# Motors.net
KiCad netlist of a schematic drawn in Altium Designer
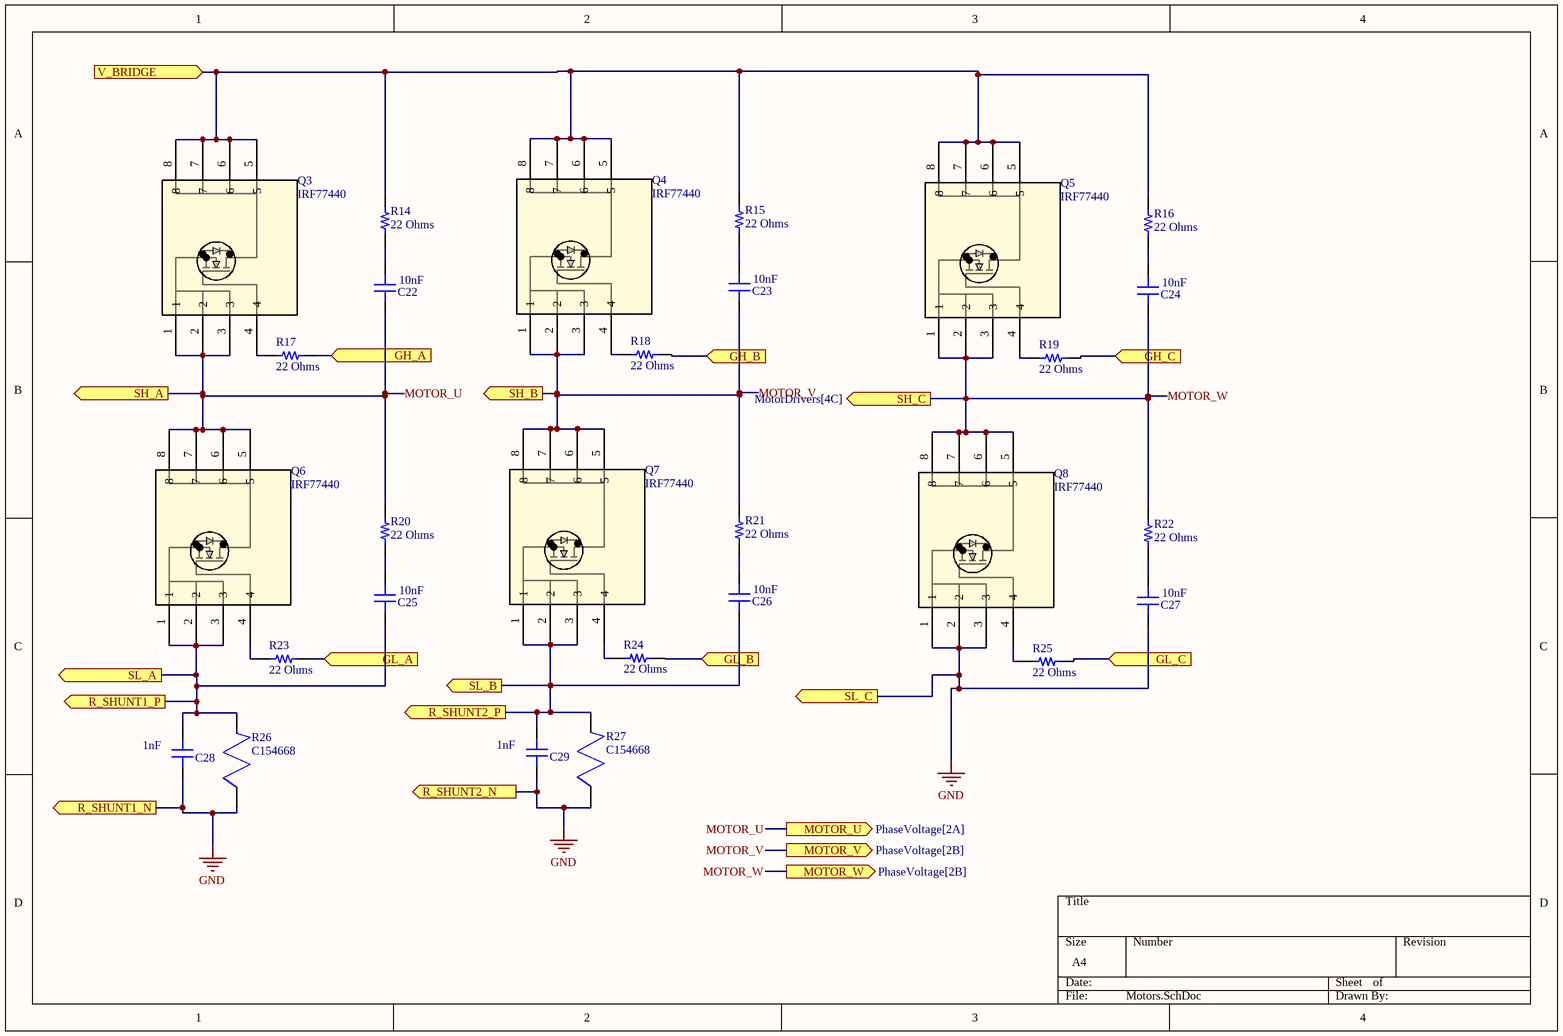
[diagram p0: Motors.SchDoc]

(export (version "E")
  (design (tool "Eeschema 10.0.6"))
  (components
    (comp (ref "C22")
      (value "10nF")
      (footprint "CAP 0603_1608")
      (description "CAP CER 1000PF 10V X7R 0603")
      (fields (field (name "PART NUMBER") "0603ZC102KAT2A") (field (name "MANUFACTURER") "AVX Corporation"))
      (libsource (lib "Celestial Altium Library - altium_library (4)") (part "Capacitor"))
    )
    (comp (ref "C23")
      (value "10nF")
      (footprint "CAP 0603_1608")
      (description "CAP CER 1000PF 10V X7R 0603")
      (fields (field (name "PART NUMBER") "0603ZC102KAT2A") (field (name "MANUFACTURER") "AVX Corporation"))
      (libsource (lib "Celestial Altium Library - altium_library (4)") (part "Capacitor"))
    )
    (comp (ref "C24")
      (value "10nF")
      (footprint "CAP 0603_1608")
      (description "CAP CER 1000PF 10V X7R 0603")
      (fields (field (name "PART NUMBER") "0603ZC102KAT2A") (field (name "MANUFACTURER") "AVX Corporation"))
      (libsource (lib "Celestial Altium Library - altium_library (4)") (part "Capacitor"))
    )
    (comp (ref "C25")
      (value "10nF")
      (footprint "CAP 0603_1608")
      (description "CAP CER 1000PF 10V X7R 0603")
      (fields (field (name "PART NUMBER") "0603ZC102KAT2A") (field (name "MANUFACTURER") "AVX Corporation"))
      (libsource (lib "Celestial Altium Library - altium_library (4)") (part "Capacitor"))
    )
    (comp (ref "C26")
      (value "10nF")
      (footprint "CAP 0603_1608")
      (description "CAP CER 1000PF 10V X7R 0603")
      (fields (field (name "PART NUMBER") "0603ZC102KAT2A") (field (name "MANUFACTURER") "AVX Corporation"))
      (libsource (lib "Celestial Altium Library - altium_library (4)") (part "Capacitor"))
    )
    (comp (ref "C27")
      (value "10nF")
      (footprint "CAP 0603_1608")
      (description "CAP CER 1000PF 10V X7R 0603")
      (fields (field (name "PART NUMBER") "0603ZC102KAT2A") (field (name "MANUFACTURER") "AVX Corporation"))
      (libsource (lib "Celestial Altium Library - altium_library (4)") (part "Capacitor"))
    )
    (comp (ref "C28")
      (value "1nF")
      (footprint "CAP 0603_1608")
      (description "CAP CER 1000PF 10V X7R 0603")
      (fields (field (name "PART NUMBER") "0603ZC102KAT2A") (field (name "MANUFACTURER") "AVX Corporation"))
      (libsource (lib "Celestial Altium Library - altium_library (4)") (part "Capacitor"))
    )
    (comp (ref "C29")
      (value "1nF")
      (footprint "CAP 0603_1608")
      (description "CAP CER 1000PF 10V X7R 0603")
      (fields (field (name "PART NUMBER") "0603ZC102KAT2A") (field (name "MANUFACTURER") "AVX Corporation"))
      (libsource (lib "Celestial Altium Library - altium_library (4)") (part "Capacitor"))
    )
    (comp (ref "Q3") (value "IRF77440") (footprint "IRF77440") (libsource (lib "Schlib1") (part "IRF77440")))
    (comp (ref "Q4") (value "IRF77440") (footprint "IRF77440") (libsource (lib "Schlib1") (part "IRF77440")))
    (comp (ref "Q5") (value "IRF77440") (footprint "IRF77440") (libsource (lib "Schlib1") (part "IRF77440")))
    (comp (ref "Q6") (value "IRF77440") (footprint "IRF77440") (libsource (lib "Schlib1") (part "IRF77440")))
    (comp (ref "Q7") (value "IRF77440") (footprint "IRF77440") (libsource (lib "Schlib1") (part "IRF77440")))
    (comp (ref "Q8") (value "IRF77440") (footprint "IRF77440") (libsource (lib "Schlib1") (part "IRF77440")))
    (comp (ref "R14")
      (value "22 Ohms")
      (footprint "RES 0402_1005")
      (description "ANTI-SURGE CHIP RESISTORS")
      (fields (field (name "PART NUMBER") "ESR01MZPF47R0") (field (name "MANUFACTURER") "Rohm Semiconductor"))
      (libsource (lib "Celestial Altium Library - altium_library (4)") (part "Resistor"))
    )
    (comp (ref "R15")
      (value "22 Ohms")
      (footprint "RES 0402_1005")
      (description "ANTI-SURGE CHIP RESISTORS")
      (fields (field (name "PART NUMBER") "ESR01MZPF47R0") (field (name "MANUFACTURER") "Rohm Semiconductor"))
      (libsource (lib "Celestial Altium Library - altium_library (4)") (part "Resistor"))
    )
    (comp (ref "R16")
      (value "22 Ohms")
      (footprint "RES 0402_1005")
      (description "ANTI-SURGE CHIP RESISTORS")
      (fields (field (name "PART NUMBER") "ESR01MZPF47R0") (field (name "MANUFACTURER") "Rohm Semiconductor"))
      (libsource (lib "Celestial Altium Library - altium_library (4)") (part "Resistor"))
    )
    (comp (ref "R17")
      (value "22 Ohms")
      (footprint "RES 0402_1005")
      (description "ANTI-SURGE CHIP RESISTORS")
      (fields (field (name "PART NUMBER") "ESR01MZPF47R0") (field (name "MANUFACTURER") "Rohm Semiconductor"))
      (libsource (lib "Celestial Altium Library - altium_library (4)") (part "Resistor"))
    )
    (comp (ref "R18")
      (value "22 Ohms")
      (footprint "RES 0402_1005")
      (description "ANTI-SURGE CHIP RESISTORS")
      (fields (field (name "PART NUMBER") "ESR01MZPF47R0") (field (name "MANUFACTURER") "Rohm Semiconductor"))
      (libsource (lib "Celestial Altium Library - altium_library (4)") (part "Resistor"))
    )
    (comp (ref "R19")
      (value "22 Ohms")
      (footprint "RES 0402_1005")
      (description "ANTI-SURGE CHIP RESISTORS")
      (fields (field (name "PART NUMBER") "ESR01MZPF47R0") (field (name "MANUFACTURER") "Rohm Semiconductor"))
      (libsource (lib "Celestial Altium Library - altium_library (4)") (part "Resistor"))
    )
    (comp (ref "R20")
      (value "22 Ohms")
      (footprint "RES 0402_1005")
      (description "ANTI-SURGE CHIP RESISTORS")
      (fields (field (name "PART NUMBER") "ESR01MZPF47R0") (field (name "MANUFACTURER") "Rohm Semiconductor"))
      (libsource (lib "Celestial Altium Library - altium_library (4)") (part "Resistor"))
    )
    (comp (ref "R21")
      (value "22 Ohms")
      (footprint "RES 0402_1005")
      (description "ANTI-SURGE CHIP RESISTORS")
      (fields (field (name "PART NUMBER") "ESR01MZPF47R0") (field (name "MANUFACTURER") "Rohm Semiconductor"))
      (libsource (lib "Celestial Altium Library - altium_library (4)") (part "Resistor"))
    )
    (comp (ref "R22")
      (value "22 Ohms")
      (footprint "RES 0402_1005")
      (description "ANTI-SURGE CHIP RESISTORS")
      (fields (field (name "PART NUMBER") "ESR01MZPF47R0") (field (name "MANUFACTURER") "Rohm Semiconductor"))
      (libsource (lib "Celestial Altium Library - altium_library (4)") (part "Resistor"))
    )
    (comp (ref "R23")
      (value "22 Ohms")
      (footprint "RES 0402_1005")
      (description "ANTI-SURGE CHIP RESISTORS")
      (fields (field (name "PART NUMBER") "ESR01MZPF47R0") (field (name "MANUFACTURER") "Rohm Semiconductor"))
      (libsource (lib "Celestial Altium Library - altium_library (4)") (part "Resistor"))
    )
    (comp (ref "R24")
      (value "22 Ohms")
      (footprint "RES 0402_1005")
      (description "ANTI-SURGE CHIP RESISTORS")
      (fields (field (name "PART NUMBER") "ESR01MZPF47R0") (field (name "MANUFACTURER") "Rohm Semiconductor"))
      (libsource (lib "Celestial Altium Library - altium_library (4)") (part "Resistor"))
    )
    (comp (ref "R25")
      (value "22 Ohms")
      (footprint "RES 0402_1005")
      (description "ANTI-SURGE CHIP RESISTORS")
      (fields (field (name "PART NUMBER") "ESR01MZPF47R0") (field (name "MANUFACTURER") "Rohm Semiconductor"))
      (libsource (lib "Celestial Altium Library - altium_library (4)") (part "Resistor"))
    )
    (comp (ref "R26") (value "C154668") (footprint "C154668") (libsource (lib "Schlib1") (part "C154668")))
    (comp (ref "R27") (value "C154668") (footprint "C154668") (libsource (lib "Schlib1") (part "C154668")))
  )
  (nets
    (net (code "1") (name "/GH_A") (class "Default")
      (node (ref "R17") (pin "2") (pinfunction "2_2") (pintype "passive"))
    )
    (net (code "2") (name "/GH_B") (class "Default")
      (node (ref "R18") (pin "2") (pinfunction "2_2") (pintype "passive"))
    )
    (net (code "3") (name "/GH_C") (class "Default")
      (node (ref "R19") (pin "2") (pinfunction "2_2") (pintype "passive"))
    )
    (net (code "4") (name "/GL_A") (class "Default")
      (node (ref "R23") (pin "2") (pinfunction "2_2") (pintype "passive"))
    )
    (net (code "5") (name "/GL_B") (class "Default")
      (node (ref "R24") (pin "2") (pinfunction "2_2") (pintype "passive"))
    )
    (net (code "6") (name "/GL_C") (class "Default")
      (node (ref "R25") (pin "2") (pinfunction "2_2") (pintype "passive"))
    )
    (net (code "7") (name "/MOTOR_U") (class "Default")
      (node (ref "C22") (pin "1") (pinfunction "1_1") (pintype "passive"))
      (node (ref "Q3") (pin "1") (pinfunction "1_1") (pintype "passive"))
      (node (ref "Q3") (pin "2") (pinfunction "2_2") (pintype "passive"))
      (node (ref "Q3") (pin "3") (pinfunction "3_3") (pintype "passive"))
      (node (ref "Q6") (pin "5") (pinfunction "5_5") (pintype "passive"))
      (node (ref "Q6") (pin "6") (pinfunction "6_6") (pintype "passive"))
      (node (ref "Q6") (pin "7") (pinfunction "7_7") (pintype "passive"))
      (node (ref "Q6") (pin "8") (pinfunction "8_8") (pintype "passive"))
      (node (ref "R20") (pin "2") (pinfunction "2_2") (pintype "passive"))
    )
    (net (code "8") (name "/MOTOR_V") (class "Default")
      (node (ref "C23") (pin "1") (pinfunction "1_1") (pintype "passive"))
      (node (ref "Q4") (pin "1") (pinfunction "1_1") (pintype "passive"))
      (node (ref "Q4") (pin "2") (pinfunction "2_2") (pintype "passive"))
      (node (ref "Q4") (pin "3") (pinfunction "3_3") (pintype "passive"))
      (node (ref "Q7") (pin "5") (pinfunction "5_5") (pintype "passive"))
      (node (ref "Q7") (pin "6") (pinfunction "6_6") (pintype "passive"))
      (node (ref "Q7") (pin "7") (pinfunction "7_7") (pintype "passive"))
      (node (ref "Q7") (pin "8") (pinfunction "8_8") (pintype "passive"))
      (node (ref "R21") (pin "2") (pinfunction "2_2") (pintype "passive"))
    )
    (net (code "9") (name "/MOTOR_W") (class "Default")
      (node (ref "C24") (pin "1") (pinfunction "1_1") (pintype "passive"))
      (node (ref "Q5") (pin "1") (pinfunction "1_1") (pintype "passive"))
      (node (ref "Q5") (pin "2") (pinfunction "2_2") (pintype "passive"))
      (node (ref "Q5") (pin "3") (pinfunction "3_3") (pintype "passive"))
      (node (ref "Q8") (pin "5") (pinfunction "5_5") (pintype "passive"))
      (node (ref "Q8") (pin "6") (pinfunction "6_6") (pintype "passive"))
      (node (ref "Q8") (pin "7") (pinfunction "7_7") (pintype "passive"))
      (node (ref "Q8") (pin "8") (pinfunction "8_8") (pintype "passive"))
      (node (ref "R22") (pin "2") (pinfunction "2_2") (pintype "passive"))
    )
    (net (code "10") (name "/R_SHUNT1_P") (class "Default")
      (node (ref "C25") (pin "1") (pinfunction "1_1") (pintype "passive"))
      (node (ref "C28") (pin "2") (pinfunction "2_2") (pintype "passive"))
      (node (ref "Q6") (pin "1") (pinfunction "1_1") (pintype "passive"))
      (node (ref "Q6") (pin "2") (pinfunction "2_2") (pintype "passive"))
      (node (ref "Q6") (pin "3") (pinfunction "3_3") (pintype "passive"))
      (node (ref "R26") (pin "2") (pinfunction "0_2") (pintype "passive"))
    )
    (net (code "11") (name "/R_SHUNT2_P") (class "Default")
      (node (ref "C26") (pin "1") (pinfunction "1_1") (pintype "passive"))
      (node (ref "C29") (pin "2") (pinfunction "2_2") (pintype "passive"))
      (node (ref "Q7") (pin "1") (pinfunction "1_1") (pintype "passive"))
      (node (ref "Q7") (pin "2") (pinfunction "2_2") (pintype "passive"))
      (node (ref "Q7") (pin "3") (pinfunction "3_3") (pintype "passive"))
      (node (ref "R27") (pin "2") (pinfunction "0_2") (pintype "passive"))
    )
    (net (code "13") (name "/V_BRIDGE") (class "Default")
      (node (ref "Q3") (pin "5") (pinfunction "5_5") (pintype "passive"))
      (node (ref "Q3") (pin "6") (pinfunction "6_6") (pintype "passive"))
      (node (ref "Q3") (pin "7") (pinfunction "7_7") (pintype "passive"))
      (node (ref "Q3") (pin "8") (pinfunction "8_8") (pintype "passive"))
      (node (ref "Q4") (pin "5") (pinfunction "5_5") (pintype "passive"))
      (node (ref "Q4") (pin "6") (pinfunction "6_6") (pintype "passive"))
      (node (ref "Q4") (pin "7") (pinfunction "7_7") (pintype "passive"))
      (node (ref "Q4") (pin "8") (pinfunction "8_8") (pintype "passive"))
      (node (ref "Q5") (pin "5") (pinfunction "5_5") (pintype "passive"))
      (node (ref "Q5") (pin "6") (pinfunction "6_6") (pintype "passive"))
      (node (ref "Q5") (pin "7") (pinfunction "7_7") (pintype "passive"))
      (node (ref "Q5") (pin "8") (pinfunction "8_8") (pintype "passive"))
      (node (ref "R14") (pin "2") (pinfunction "2_2") (pintype "passive"))
      (node (ref "R15") (pin "2") (pinfunction "2_2") (pintype "passive"))
      (node (ref "R16") (pin "2") (pinfunction "2_2") (pintype "passive"))
    )
    (net (code "14") (name "GND") (class "Default")
      (node (ref "C27") (pin "1") (pinfunction "1_1") (pintype "passive"))
      (node (ref "C28") (pin "1") (pinfunction "1_1") (pintype "passive"))
      (node (ref "C29") (pin "1") (pinfunction "1_1") (pintype "passive"))
      (node (ref "Q8") (pin "1") (pinfunction "1_1") (pintype "passive"))
      (node (ref "Q8") (pin "2") (pinfunction "2_2") (pintype "passive"))
      (node (ref "Q8") (pin "3") (pinfunction "3_3") (pintype "passive"))
      (node (ref "R26") (pin "1") (pinfunction "1_1") (pintype "passive"))
      (node (ref "R27") (pin "1") (pinfunction "1_1") (pintype "passive"))
    )
    (net (code "15") (name "Net-(C22-Pad2)") (class "Default")
      (node (ref "C22") (pin "2") (pinfunction "2_2") (pintype "passive"))
      (node (ref "R14") (pin "1") (pinfunction "1_1") (pintype "passive"))
    )
    (net (code "16") (name "Net-(C23-Pad2)") (class "Default")
      (node (ref "C23") (pin "2") (pinfunction "2_2") (pintype "passive"))
      (node (ref "R15") (pin "1") (pinfunction "1_1") (pintype "passive"))
    )
    (net (code "17") (name "Net-(C24-Pad2)") (class "Default")
      (node (ref "C24") (pin "2") (pinfunction "2_2") (pintype "passive"))
      (node (ref "R16") (pin "1") (pinfunction "1_1") (pintype "passive"))
    )
    (net (code "18") (name "Net-(C25-Pad2)") (class "Default")
      (node (ref "C25") (pin "2") (pinfunction "2_2") (pintype "passive"))
      (node (ref "R20") (pin "1") (pinfunction "1_1") (pintype "passive"))
    )
    (net (code "19") (name "Net-(C26-Pad2)") (class "Default")
      (node (ref "C26") (pin "2") (pinfunction "2_2") (pintype "passive"))
      (node (ref "R21") (pin "1") (pinfunction "1_1") (pintype "passive"))
    )
    (net (code "20") (name "Net-(C27-Pad2)") (class "Default")
      (node (ref "C27") (pin "2") (pinfunction "2_2") (pintype "passive"))
      (node (ref "R22") (pin "1") (pinfunction "1_1") (pintype "passive"))
    )
    (net (code "21") (name "Net-(Q3-Pad4)") (class "Default")
      (node (ref "Q3") (pin "4") (pinfunction "4_4") (pintype "passive"))
      (node (ref "R17") (pin "1") (pinfunction "1_1") (pintype "passive"))
    )
    (net (code "22") (name "Net-(Q4-Pad4)") (class "Default")
      (node (ref "Q4") (pin "4") (pinfunction "4_4") (pintype "passive"))
      (node (ref "R18") (pin "1") (pinfunction "1_1") (pintype "passive"))
    )
    (net (code "23") (name "Net-(Q5-Pad4)") (class "Default")
      (node (ref "Q5") (pin "4") (pinfunction "4_4") (pintype "passive"))
      (node (ref "R19") (pin "1") (pinfunction "1_1") (pintype "passive"))
    )
    (net (code "24") (name "Net-(Q6-Pad4)") (class "Default")
      (node (ref "Q6") (pin "4") (pinfunction "4_4") (pintype "passive"))
      (node (ref "R23") (pin "1") (pinfunction "1_1") (pintype "passive"))
    )
    (net (code "25") (name "Net-(Q7-Pad4)") (class "Default")
      (node (ref "Q7") (pin "4") (pinfunction "4_4") (pintype "passive"))
      (node (ref "R24") (pin "1") (pinfunction "1_1") (pintype "passive"))
    )
    (net (code "26") (name "Net-(Q8-Pad4)") (class "Default")
      (node (ref "Q8") (pin "4") (pinfunction "4_4") (pintype "passive"))
      (node (ref "R25") (pin "1") (pinfunction "1_1") (pintype "passive"))
    )
  )
)
